# console_v3.net
KiCad netlist of a schematic drawn in EAGLE
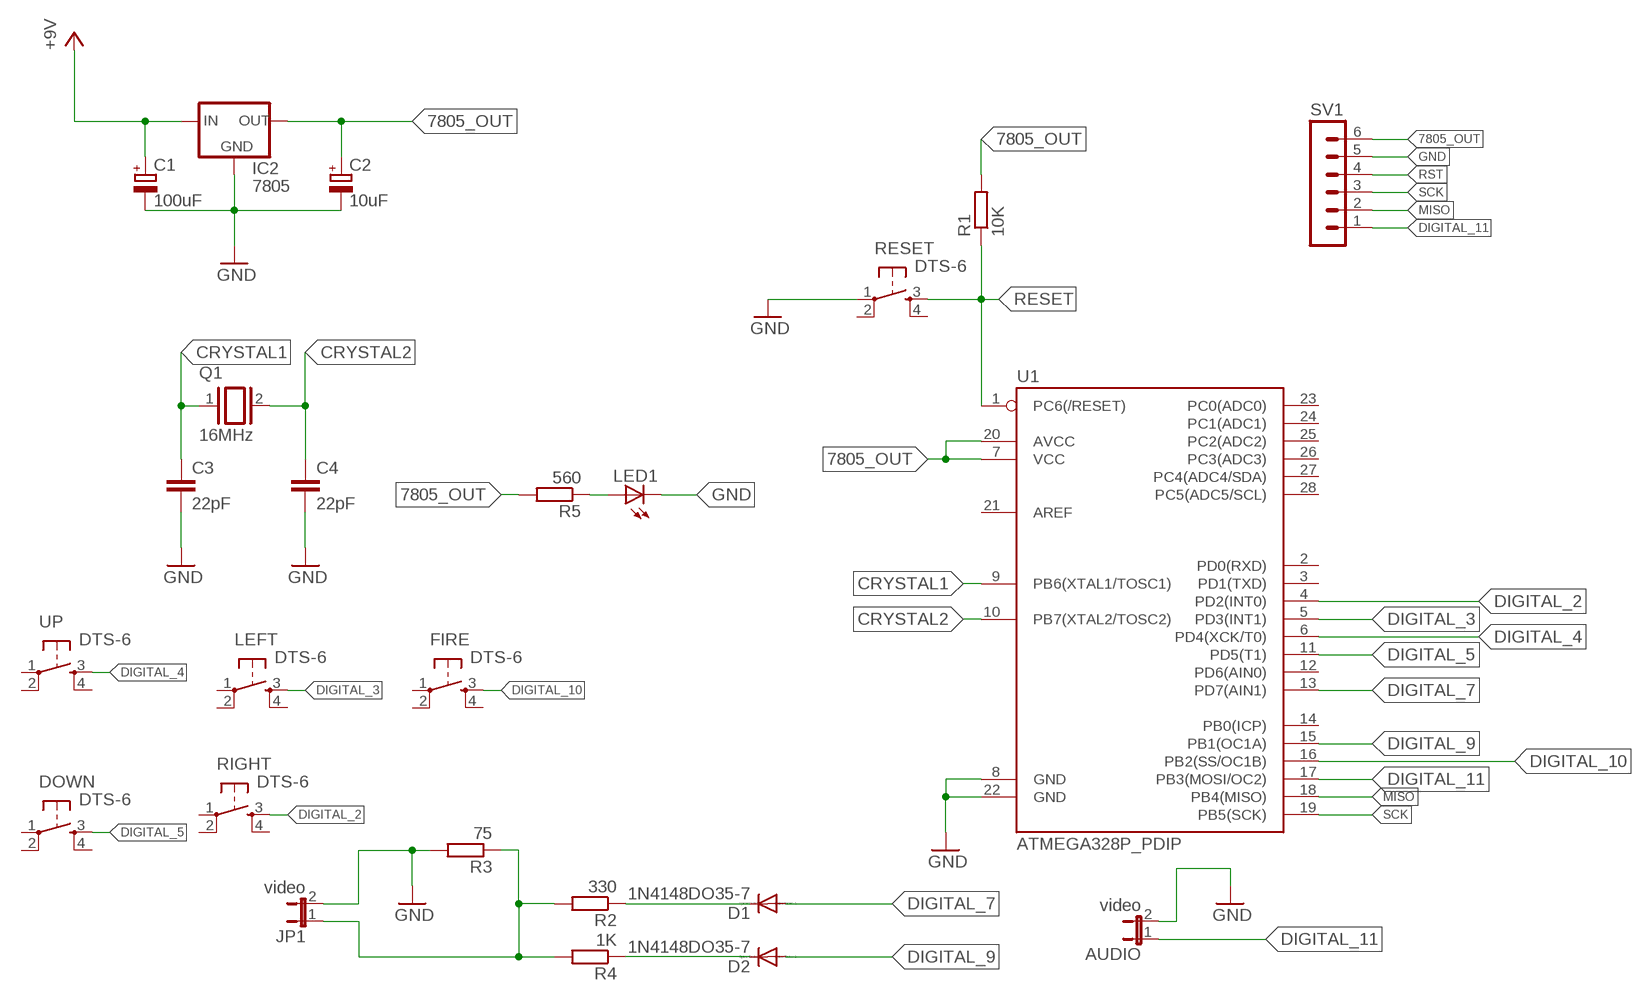
[diagram p0: schematic, sheet 1]

(export (version "E")
  (design (tool "Eeschema 10.0.6"))
  (components
    (comp (ref "AUDIO")
      (value "video")
      (footprint "eagle-import:JP1")
      (libsource (lib "eagle-import") (part "JP1E"))
    )
    (comp (ref "C1")
      (value "100uF")
      (footprint "eagle-import:E2,5-6E")
      (libsource (lib "eagle-import") (part "CPOL-EUE2,5-6E"))
    )
    (comp (ref "C2")
      (value "10uF")
      (footprint "eagle-import:E2,5-6E")
      (libsource (lib "eagle-import") (part "CPOL-EUE2,5-6E"))
    )
    (comp (ref "C3")
      (value "22pF")
      (footprint "eagle-import:C2.5-3")
      (libsource (lib "eagle-import") (part "C2,5-3"))
    )
    (comp (ref "C4")
      (value "22pF")
      (footprint "eagle-import:C2.5-3")
      (libsource (lib "eagle-import") (part "C2,5-3"))
    )
    (comp (ref "D1")
      (value "1N4148DO35-7")
      (footprint "eagle-import:DO35-7")
      (libsource (lib "eagle-import") (part "1N4148DO35-7"))
    )
    (comp (ref "D2")
      (value "1N4148DO35-7")
      (footprint "eagle-import:DO35-7")
      (libsource (lib "eagle-import") (part "1N4148DO35-7"))
    )
    (comp (ref "DOWN")
      (value "DTS-6")
      (footprint "eagle-import:DTS-6")
      (libsource (lib "eagle-import") (part "DTS-6"))
    )
    (comp (ref "FIRE")
      (value "DTS-6")
      (footprint "eagle-import:DTS-6")
      (libsource (lib "eagle-import") (part "DTS-6"))
    )
    (comp (ref "IC2")
      (value "7805")
      (footprint "eagle-import:78MXXL")
      (libsource (lib "eagle-import") (part "78MXXL"))
    )
    (comp (ref "JP1")
      (value "video")
      (footprint "eagle-import:JP1")
      (libsource (lib "eagle-import") (part "JP1E"))
    )
    (comp (ref "LED1")
      (value "LED3MM")
      (footprint "eagle-import:LED3MM")
      (libsource (lib "eagle-import") (part "LED3MM"))
    )
    (comp (ref "LEFT")
      (value "DTS-6")
      (footprint "eagle-import:DTS-6")
      (libsource (lib "eagle-import") (part "DTS-6"))
    )
    (comp (ref "Q1")
      (value "16MHz")
      (footprint "eagle-import:QS")
      (libsource (lib "eagle-import") (part "XTAL/S"))
    )
    (comp (ref "R1")
      (value "10K")
      (footprint "eagle-import:0204_5")
      (libsource (lib "eagle-import") (part "R-EU_0204/5"))
    )
    (comp (ref "R2")
      (value "330")
      (footprint "eagle-import:0204_5")
      (libsource (lib "eagle-import") (part "R-EU_0204/5"))
    )
    (comp (ref "R3")
      (value "75")
      (footprint "eagle-import:0204_5")
      (libsource (lib "eagle-import") (part "R-EU_0204/5"))
    )
    (comp (ref "R4")
      (value "1K")
      (footprint "eagle-import:0204_5")
      (libsource (lib "eagle-import") (part "R-EU_0204/5"))
    )
    (comp (ref "R5")
      (value "560")
      (footprint "eagle-import:0204_5")
      (libsource (lib "eagle-import") (part "R-EU_0204/5"))
    )
    (comp (ref "RESET")
      (value "DTS-6")
      (footprint "eagle-import:DTS-6")
      (libsource (lib "eagle-import") (part "DTS-6"))
    )
    (comp (ref "RIGHT")
      (value "DTS-6")
      (footprint "eagle-import:DTS-6")
      (libsource (lib "eagle-import") (part "DTS-6"))
    )
    (comp (ref "SV1")
      (value "MA06-1")
      (footprint "eagle-import:MA06-1")
      (libsource (lib "eagle-import") (part "MA06-1"))
    )
    (comp (ref "U1")
      (value "ATMEGA328P_PDIP")
      (footprint "eagle-import:DIL28-3")
      (libsource (lib "eagle-import") (part "ATMEGA328P_PDIP"))
    )
    (comp (ref "UP")
      (value "DTS-6")
      (footprint "eagle-import:DTS-6")
      (libsource (lib "eagle-import") (part "DTS-6"))
    )
  )
  (nets
    (net (code "1") (name "+9V") (class "Default")
      (node (ref "C1") (pin "+") (pinfunction "+_+") (pintype "passive"))
      (node (ref "IC2") (pin "IN") (pinfunction "IN_IN") (pintype "input"))
    )
    (net (code "2") (name "7805_OUT") (class "Default")
      (node (ref "C2") (pin "+") (pinfunction "+_+") (pintype "passive"))
      (node (ref "IC2") (pin "OUT") (pinfunction "OUT_OUT") (pintype "passive"))
      (node (ref "R1") (pin "2") (pinfunction "2_2") (pintype "passive"))
      (node (ref "R5") (pin "2") (pinfunction "2_2") (pintype "passive"))
      (node (ref "SV1") (pin "6") (pinfunction "6_6") (pintype "passive"))
      (node (ref "U1") (pin "20") (pinfunction "AVCC_20") (pintype "bidirectional"))
      (node (ref "U1") (pin "7") (pinfunction "VCC_7") (pintype "bidirectional"))
    )
    (net (code "3") (name "CRYSTAL1") (class "Default")
      (node (ref "C3") (pin "1") (pinfunction "1_1") (pintype "passive"))
      (node (ref "Q1") (pin "1") (pinfunction "1_1") (pintype "passive"))
      (node (ref "U1") (pin "9") (pinfunction "PB6(XTAL1/TOSC1)_9") (pintype "bidirectional"))
    )
    (net (code "4") (name "CRYSTAL2") (class "Default")
      (node (ref "C4") (pin "1") (pinfunction "1_1") (pintype "passive"))
      (node (ref "Q1") (pin "2") (pinfunction "2_2") (pintype "passive"))
      (node (ref "U1") (pin "10") (pinfunction "PB7(XTAL2/TOSC2)_10") (pintype "bidirectional"))
    )
    (net (code "5") (name "DIGITAL_2") (class "Default")
      (node (ref "RIGHT") (pin "3") (pinfunction "3_3") (pintype "passive"))
      (node (ref "U1") (pin "4") (pinfunction "PD2(INT0)_4") (pintype "bidirectional"))
    )
    (net (code "6") (name "DIGITAL_3") (class "Default")
      (node (ref "LEFT") (pin "3") (pinfunction "3_3") (pintype "passive"))
      (node (ref "U1") (pin "5") (pinfunction "PD3(INT1)_5") (pintype "bidirectional"))
    )
    (net (code "7") (name "DIGITAL_4") (class "Default")
      (node (ref "U1") (pin "6") (pinfunction "PD4(XCK/T0)_6") (pintype "bidirectional"))
      (node (ref "UP") (pin "3") (pinfunction "3_3") (pintype "passive"))
    )
    (net (code "8") (name "DIGITAL_5") (class "Default")
      (node (ref "DOWN") (pin "3") (pinfunction "3_3") (pintype "passive"))
      (node (ref "U1") (pin "11") (pinfunction "PD5(T1)_11") (pintype "bidirectional"))
    )
    (net (code "9") (name "DIGITAL_7") (class "Default")
      (node (ref "D1") (pin "A") (pinfunction "A_A") (pintype "passive"))
      (node (ref "U1") (pin "13") (pinfunction "PD7(AIN1)_13") (pintype "bidirectional"))
    )
    (net (code "10") (name "DIGITAL_9") (class "Default")
      (node (ref "D2") (pin "A") (pinfunction "A_A") (pintype "passive"))
      (node (ref "U1") (pin "15") (pinfunction "PB1(OC1A)_15") (pintype "bidirectional"))
    )
    (net (code "11") (name "DIGITAL_10") (class "Default")
      (node (ref "FIRE") (pin "3") (pinfunction "3_3") (pintype "passive"))
      (node (ref "U1") (pin "16") (pinfunction "PB2(SS/OC1B)_16") (pintype "bidirectional"))
    )
    (net (code "12") (name "DIGITAL_11") (class "Default")
      (node (ref "AUDIO") (pin "1") (pinfunction "1_1") (pintype "passive"))
      (node (ref "SV1") (pin "1") (pinfunction "1_1") (pintype "passive"))
      (node (ref "U1") (pin "17") (pinfunction "PB3(MOSI/OC2)_17") (pintype "bidirectional"))
    )
    (net (code "13") (name "GND") (class "Default")
      (node (ref "AUDIO") (pin "2") (pinfunction "2_2") (pintype "passive"))
      (node (ref "C1") (pin "-") (pinfunction "-_-") (pintype "passive"))
      (node (ref "C2") (pin "-") (pinfunction "-_-") (pintype "passive"))
      (node (ref "C3") (pin "2") (pinfunction "2_2") (pintype "passive"))
      (node (ref "C4") (pin "2") (pinfunction "2_2") (pintype "passive"))
      (node (ref "IC2") (pin "GND") (pinfunction "GND_GND") (pintype "input"))
      (node (ref "JP1") (pin "2") (pinfunction "2_2") (pintype "passive"))
      (node (ref "LED1") (pin "K") (pinfunction "C_K") (pintype "passive"))
      (node (ref "R3") (pin "2") (pinfunction "2_2") (pintype "passive"))
      (node (ref "RESET") (pin "1") (pinfunction "1_1") (pintype "passive"))
      (node (ref "SV1") (pin "5") (pinfunction "5_5") (pintype "passive"))
      (node (ref "U1") (pin "22") (pinfunction "GND_22") (pintype "bidirectional"))
      (node (ref "U1") (pin "8") (pinfunction "GND_8") (pintype "bidirectional"))
    )
    (net (code "14") (name "MISO") (class "Default")
      (node (ref "SV1") (pin "2") (pinfunction "2_2") (pintype "passive"))
      (node (ref "U1") (pin "18") (pinfunction "PB4(MISO)_18") (pintype "bidirectional"))
    )
    (net (code "15") (name "Net-(D1-PadC)") (class "Default")
      (node (ref "D1") (pin "C") (pinfunction "C_C") (pintype "passive"))
      (node (ref "R2") (pin "1") (pinfunction "1_1") (pintype "passive"))
    )
    (net (code "16") (name "Net-(D2-PadC)") (class "Default")
      (node (ref "D2") (pin "C") (pinfunction "C_C") (pintype "passive"))
      (node (ref "R4") (pin "1") (pinfunction "1_1") (pintype "passive"))
    )
    (net (code "17") (name "Net-(JP1-Pad1)") (class "Default")
      (node (ref "JP1") (pin "1") (pinfunction "1_1") (pintype "passive"))
      (node (ref "R2") (pin "2") (pinfunction "2_2") (pintype "passive"))
      (node (ref "R3") (pin "1") (pinfunction "1_1") (pintype "passive"))
      (node (ref "R4") (pin "2") (pinfunction "2_2") (pintype "passive"))
    )
    (net (code "18") (name "Net-(LED1-PadA)") (class "Default")
      (node (ref "LED1") (pin "A") (pinfunction "A_A") (pintype "passive"))
      (node (ref "R5") (pin "1") (pinfunction "1_1") (pintype "passive"))
    )
    (net (code "19") (name "RESET") (class "Default")
      (node (ref "R1") (pin "1") (pinfunction "1_1") (pintype "passive"))
      (node (ref "RESET") (pin "3") (pinfunction "3_3") (pintype "passive"))
      (node (ref "U1") (pin "1") (pinfunction "PC6(/RESET)_1") (pintype "bidirectional"))
    )
    (net (code "20") (name "RST") (class "Default")
      (node (ref "SV1") (pin "4") (pinfunction "4_4") (pintype "passive"))
    )
    (net (code "21") (name "SCK") (class "Default")
      (node (ref "SV1") (pin "3") (pinfunction "3_3") (pintype "passive"))
      (node (ref "U1") (pin "19") (pinfunction "PB5(SCK)_19") (pintype "bidirectional"))
    )
    (net (code "22") (name "unconnected-(DOWN-Pad1)") (class "Default")
      (node (ref "DOWN") (pin "1") (pinfunction "1_1") (pintype "passive"))
    )
    (net (code "23") (name "unconnected-(DOWN-Pad2)") (class "Default")
      (node (ref "DOWN") (pin "2") (pinfunction "2_2") (pintype "passive"))
    )
    (net (code "24") (name "unconnected-(DOWN-Pad4)") (class "Default")
      (node (ref "DOWN") (pin "4") (pinfunction "4_4") (pintype "passive"))
    )
    (net (code "25") (name "unconnected-(FIRE-Pad1)") (class "Default")
      (node (ref "FIRE") (pin "1") (pinfunction "1_1") (pintype "passive"))
    )
    (net (code "26") (name "unconnected-(FIRE-Pad2)") (class "Default")
      (node (ref "FIRE") (pin "2") (pinfunction "2_2") (pintype "passive"))
    )
    (net (code "27") (name "unconnected-(FIRE-Pad4)") (class "Default")
      (node (ref "FIRE") (pin "4") (pinfunction "4_4") (pintype "passive"))
    )
    (net (code "28") (name "unconnected-(LEFT-Pad1)") (class "Default")
      (node (ref "LEFT") (pin "1") (pinfunction "1_1") (pintype "passive"))
    )
    (net (code "29") (name "unconnected-(LEFT-Pad2)") (class "Default")
      (node (ref "LEFT") (pin "2") (pinfunction "2_2") (pintype "passive"))
    )
    (net (code "30") (name "unconnected-(LEFT-Pad4)") (class "Default")
      (node (ref "LEFT") (pin "4") (pinfunction "4_4") (pintype "passive"))
    )
    (net (code "31") (name "unconnected-(RESET-Pad2)") (class "Default")
      (node (ref "RESET") (pin "2") (pinfunction "2_2") (pintype "passive"))
    )
    (net (code "32") (name "unconnected-(RESET-Pad4)") (class "Default")
      (node (ref "RESET") (pin "4") (pinfunction "4_4") (pintype "passive"))
    )
    (net (code "33") (name "unconnected-(RIGHT-Pad1)") (class "Default")
      (node (ref "RIGHT") (pin "1") (pinfunction "1_1") (pintype "passive"))
    )
    (net (code "34") (name "unconnected-(RIGHT-Pad2)") (class "Default")
      (node (ref "RIGHT") (pin "2") (pinfunction "2_2") (pintype "passive"))
    )
    (net (code "35") (name "unconnected-(RIGHT-Pad4)") (class "Default")
      (node (ref "RIGHT") (pin "4") (pinfunction "4_4") (pintype "passive"))
    )
    (net (code "36") (name "unconnected-(U1-AREF-Pad21)") (class "Default")
      (node (ref "U1") (pin "21") (pinfunction "AREF_21") (pintype "bidirectional"))
    )
    (net (code "37") (name "unconnected-(U1-PB0(ICP)-Pad14)") (class "Default")
      (node (ref "U1") (pin "14") (pinfunction "PB0(ICP)_14") (pintype "bidirectional"))
    )
    (net (code "38") (name "unconnected-(U1-PC0(ADC0)-Pad23)") (class "Default")
      (node (ref "U1") (pin "23") (pinfunction "PC0(ADC0)_23") (pintype "bidirectional"))
    )
    (net (code "39") (name "unconnected-(U1-PC1(ADC1)-Pad24)") (class "Default")
      (node (ref "U1") (pin "24") (pinfunction "PC1(ADC1)_24") (pintype "bidirectional"))
    )
    (net (code "40") (name "unconnected-(U1-PC2(ADC2)-Pad25)") (class "Default")
      (node (ref "U1") (pin "25") (pinfunction "PC2(ADC2)_25") (pintype "bidirectional"))
    )
    (net (code "41") (name "unconnected-(U1-PC3(ADC3)-Pad26)") (class "Default")
      (node (ref "U1") (pin "26") (pinfunction "PC3(ADC3)_26") (pintype "bidirectional"))
    )
    (net (code "42") (name "unconnected-(U1-PC4(ADC4{slash}SDA)-Pad27)") (class "Default")
      (node (ref "U1") (pin "27") (pinfunction "PC4(ADC4/SDA)_27") (pintype "bidirectional"))
    )
    (net (code "43") (name "unconnected-(U1-PC5(ADC5{slash}SCL)-Pad28)") (class "Default")
      (node (ref "U1") (pin "28") (pinfunction "PC5(ADC5/SCL)_28") (pintype "bidirectional"))
    )
    (net (code "44") (name "unconnected-(U1-PD0(RXD)-Pad2)") (class "Default")
      (node (ref "U1") (pin "2") (pinfunction "PD0(RXD)_2") (pintype "bidirectional"))
    )
    (net (code "45") (name "unconnected-(U1-PD1(TXD)-Pad3)") (class "Default")
      (node (ref "U1") (pin "3") (pinfunction "PD1(TXD)_3") (pintype "bidirectional"))
    )
    (net (code "46") (name "unconnected-(U1-PD6(AIN0)-Pad12)") (class "Default")
      (node (ref "U1") (pin "12") (pinfunction "PD6(AIN0)_12") (pintype "bidirectional"))
    )
    (net (code "47") (name "unconnected-(UP-Pad1)") (class "Default")
      (node (ref "UP") (pin "1") (pinfunction "1_1") (pintype "passive"))
    )
    (net (code "48") (name "unconnected-(UP-Pad2)") (class "Default")
      (node (ref "UP") (pin "2") (pinfunction "2_2") (pintype "passive"))
    )
    (net (code "49") (name "unconnected-(UP-Pad4)") (class "Default")
      (node (ref "UP") (pin "4") (pinfunction "4_4") (pintype "passive"))
    )
  )
)
